# 2_astabilny_generator_sygnalu.net
KiCad netlist of a schematic drawn in Altium Designer
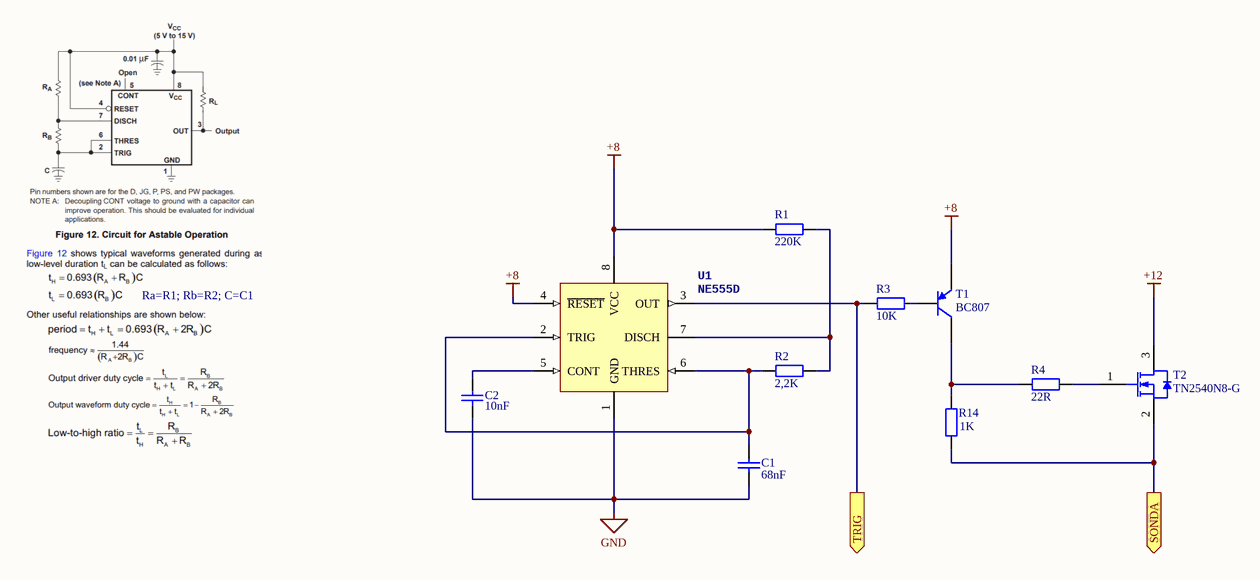
[diagram p0: 2_astabilny generator sygnalu.SchDoc]

(export (version "E")
  (design (tool "Eeschema 10.0.6"))
  (components
    (comp (ref "C1")
      (value "VJ0603Y683KXJCW1BC")
      (footprint "CAPC1608X95X40NL15T15")
      (fields (field (name "MANUFACTURER") "Vitramon") (field (name "CAPACITANCE") "68nF"))
      (libsource (lib "Altium Content Vault") (part "CAP"))
    )
    (comp (ref "C2")
      (value "VJ0603Y103KNAAO")
      (footprint "CAPC1608X92X38NL15T08")
      (fields (field (name "MANUFACTURER") "Vitramon") (field (name "CAPACITANCE") "10nF"))
      (libsource (lib "Altium Content Vault") (part "CAP"))
    )
    (comp (ref "R1")
      (value "220K")
      (footprint "R1206")
      (description "Resistor")
      (fields (field (name "Comment") "1206S4J0224T5E@TME"))
      (libsource (lib "MT_Library") (part "Res"))
    )
    (comp (ref "R2")
      (value "2,2K")
      (footprint "R1206")
      (description "Resistor")
      (fields (field (name "Comment") "1206S4J0222T5E@TME"))
      (libsource (lib "MT_Library") (part "Res"))
    )
    (comp (ref "R3")
      (value "10K")
      (footprint "R1206")
      (description "Resistor")
      (fields (field (name "Comment") "1206S4J0103T5E@TME"))
      (libsource (lib "MT_Library") (part "Res"))
    )
    (comp (ref "R4")
      (value "22R")
      (footprint "R1206")
      (description "Resistor")
      (fields (field (name "Comment") "1206S4J0220T5E@TME"))
      (libsource (lib "MT_Library") (part "Res"))
    )
    (comp (ref "R14")
      (value "1K")
      (footprint "R1206")
      (description "Resistor")
      (fields (field (name "Comment") "1206S4J0102T5E@TME"))
      (libsource (lib "MT_Library") (part "Res"))
    )
    (comp (ref "T1")
      (value "BC807")
      (footprint "ONSC-SOT-23-3-318-08_V")
      (description "General Purpose Transistor, PNP Silicon, 3-Pin SOT-23, Pb-Free, Tape and Reel")
      (fields (field (name "MANUFACTURER") "On Semiconductor") (field (name "PARTNUMBER") "BC807-25LT1G"))
      (libsource (lib "Altium Content Vault") (part "ONSC-PNP-B1E2C3-3"))
    )
    (comp (ref "T2")
      (value "TN2540N8-G")
      (footprint "FAIR-SOT23-3_A_V")
      (fields (field (name "MANUFACTURER") "FairchildSemiconductor"))
      (libsource (lib "Altium Content Vault") (part "NEMOS-GSD-3"))
    )
    (comp (ref "U1")
      (value "NE555D")
      (footprint "D0008A_N")
      (description "Precision Timer, 4.5 to 16 V, 0 to 70 degC, 8-Pin SOIC (D), Green (RoHS & no Sb/Br), Tube")
      (fields (field (name "PARTNUMBER") "NE555") (field (name "MANUFACTURER") "Texas Instruments"))
      (libsource (lib "NE555D") (part "CMP-2000-06840-1"))
    )
  )
  (nets
    (net (code "1") (name "+8") (class "Default")
      (node (ref "R1") (pin "1") (pinfunction "1_1") (pintype "passive"))
      (node (ref "T1") (pin "2") (pinfunction "E_2") (pintype "passive"))
      (node (ref "U1") (pin "4") (pinfunction "~{RESET}_4") (pintype "input"))
      (node (ref "U1") (pin "8") (pinfunction "VCC_8") (pintype "power_in"))
    )
    (net (code "2") (name "+12") (class "Default")
      (node (ref "T2") (pin "3") (pinfunction "D_3") (pintype "passive"))
    )
    (net (code "3") (name "/SONDA") (class "Default")
      (node (ref "R14") (pin "1") (pinfunction "1_1") (pintype "passive"))
      (node (ref "T2") (pin "2") (pinfunction "S_2") (pintype "passive"))
    )
    (net (code "4") (name "/TRIG") (class "Default")
      (node (ref "R3") (pin "1") (pinfunction "1_1") (pintype "passive"))
      (node (ref "U1") (pin "3") (pinfunction "OUT_3") (pintype "output"))
    )
    (net (code "5") (name "GND") (class "Default")
      (node (ref "C1") (pin "1") (pinfunction "1_1") (pintype "passive"))
      (node (ref "C2") (pin "1") (pinfunction "1_1") (pintype "passive"))
      (node (ref "U1") (pin "1") (pinfunction "GND_1") (pintype "power_in"))
    )
    (net (code "6") (name "Net-(T1-B)") (class "Default")
      (node (ref "R3") (pin "2") (pinfunction "2_2") (pintype "passive"))
      (node (ref "T1") (pin "1") (pinfunction "B_1") (pintype "passive"))
    )
    (net (code "7") (name "Net-(T1-C)") (class "Default")
      (node (ref "R14") (pin "2") (pinfunction "2_2") (pintype "passive"))
      (node (ref "R4") (pin "1") (pinfunction "1_1") (pintype "passive"))
      (node (ref "T1") (pin "3") (pinfunction "C_3") (pintype "passive"))
    )
    (net (code "8") (name "Net-(T2-G)") (class "Default")
      (node (ref "R4") (pin "2") (pinfunction "2_2") (pintype "passive"))
      (node (ref "T2") (pin "1") (pinfunction "G_1") (pintype "passive"))
    )
    (net (code "9") (name "Net-(U1-CONT)") (class "Default")
      (node (ref "C2") (pin "2") (pinfunction "2_2") (pintype "passive"))
      (node (ref "U1") (pin "5") (pinfunction "CONT_5") (pintype "input"))
    )
    (net (code "10") (name "Net-(U1-DISCH)") (class "Default")
      (node (ref "R1") (pin "2") (pinfunction "2_2") (pintype "passive"))
      (node (ref "R2") (pin "2") (pinfunction "2_2") (pintype "passive"))
      (node (ref "U1") (pin "7") (pinfunction "DISCH_7") (pintype "open_collector"))
    )
    (net (code "11") (name "Net-(U1-THRES)") (class "Default")
      (node (ref "C1") (pin "2") (pinfunction "2_2") (pintype "passive"))
      (node (ref "R2") (pin "1") (pinfunction "1_1") (pintype "passive"))
      (node (ref "U1") (pin "2") (pinfunction "TRIG_2") (pintype "input"))
      (node (ref "U1") (pin "6") (pinfunction "THRES_6") (pintype "input"))
    )
  )
)
